# nse5310-module.net
KiCad netlist of a schematic drawn in Altium Designer
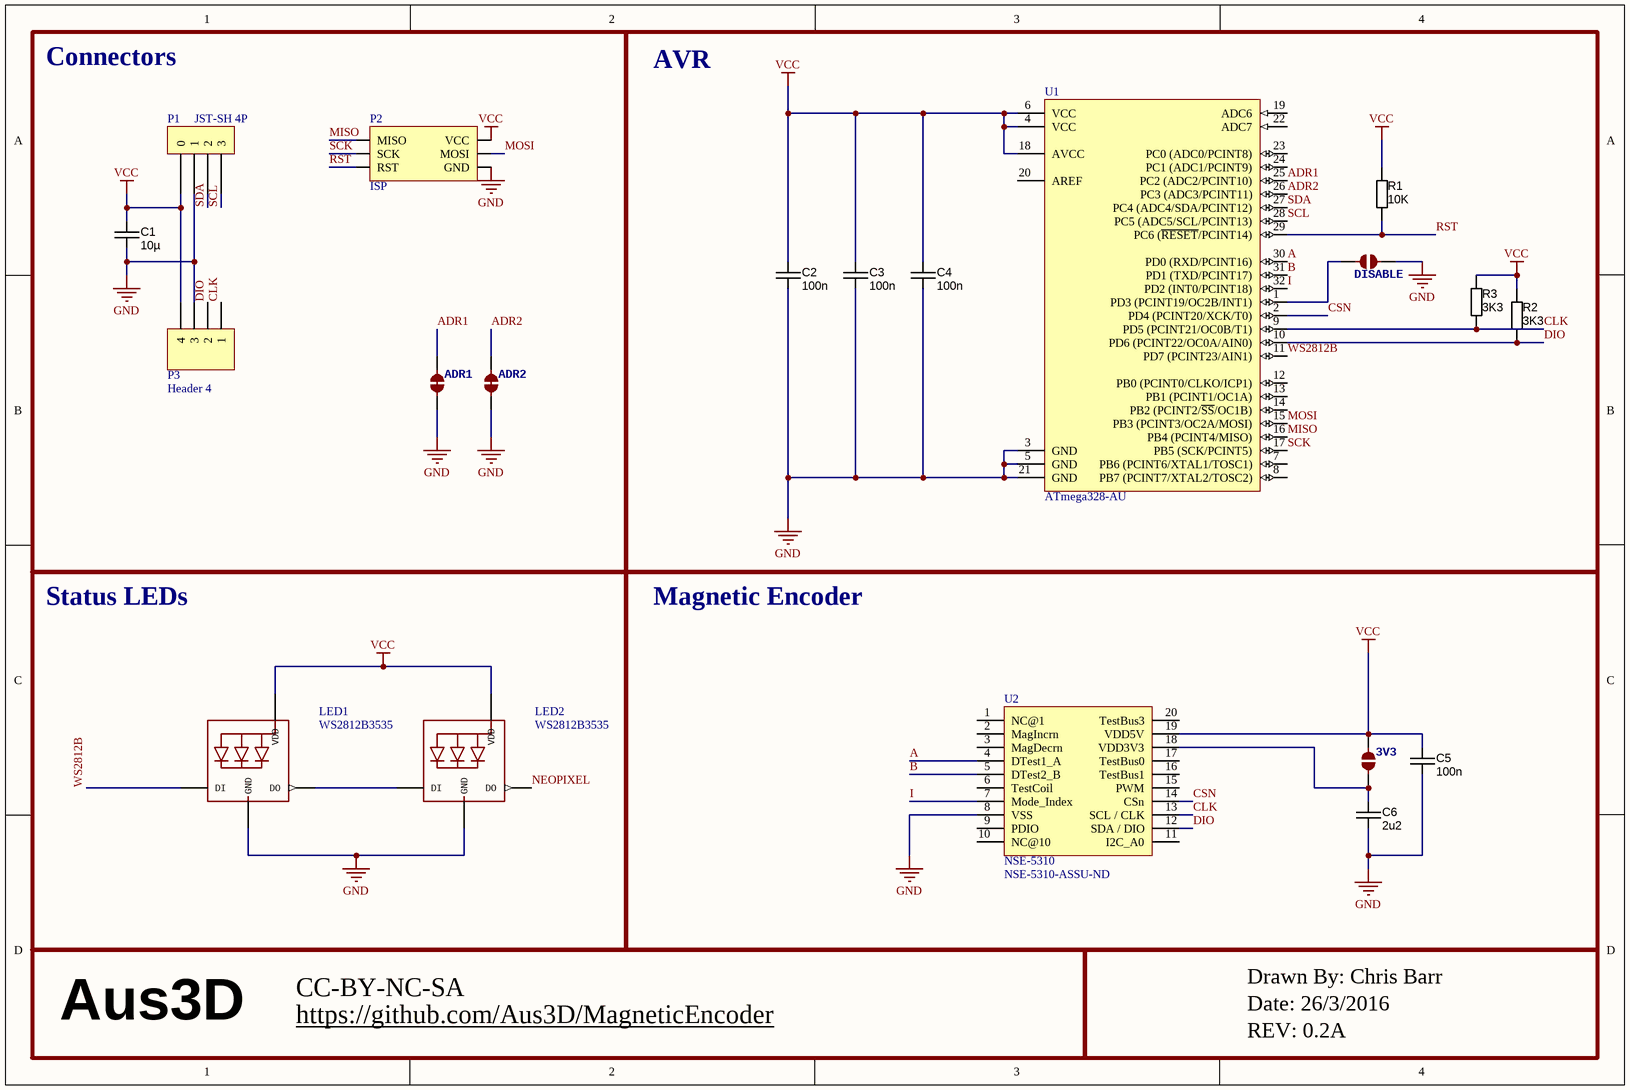
[diagram p0: nse5310-module.SchDoc]

(export (version "E")
  (design (tool "Eeschema 10.0.6"))
  (components
    (comp (ref "3V3")
      (value "JUMPER-PAD-2-NO")
      (footprint "PAD-JUMPER-2-NO_NO_SILK")
      (libsource (lib "SparkFun-Passives") (part "JUMPER-PAD-2-NO"))
    )
    (comp (ref "ADR1")
      (value "JUMPER-PAD-2-NC_BY_TRACE")
      (footprint "PAD-JUMPER-2-NC_BY_TRACE_YES_SILK")
      (libsource (lib "SparkFun-Passives") (part "JUMPER-PAD-2-NC_BY_TRACE"))
    )
    (comp (ref "ADR2")
      (value "JUMPER-PAD-2-NC_BY_TRACE")
      (footprint "PAD-JUMPER-2-NC_BY_TRACE_YES_SILK")
      (libsource (lib "SparkFun-Passives") (part "JUMPER-PAD-2-NC_BY_TRACE"))
    )
    (comp (ref "C1")
      (value "10µ")
      (footprint "CAPC2012X135N")
      (description "Capacitor SMD Cer 10uF 10% 10V X5R 0805")
      (fields (field (name "TOLERANCE") "±10%") (field (name "Comment") "approved sub OK"))
      (libsource (lib "PBL - Capacitors") (part "CAPC_10u_0805_10V"))
    )
    (comp (ref "C2")
      (value "100n")
      (footprint "CAPC1608X90N")
      (description "Capacitor SMD Cer 100nF 10% 50V X7R 0603")
      (fields (field (name "TOLERANCE") "±10%") (field (name "Comment") "approved sub OK"))
      (libsource (lib "PBL - Capacitors") (part "CAPC_100n_0603_X7R_50V_10%"))
    )
    (comp (ref "C3")
      (value "100n")
      (footprint "CAPC1608X90N")
      (description "Capacitor SMD Cer 100nF 10% 50V X7R 0603")
      (fields (field (name "TOLERANCE") "±10%") (field (name "Comment") "approved sub OK"))
      (libsource (lib "PBL - Capacitors") (part "CAPC_100n_0603_X7R_50V_10%"))
    )
    (comp (ref "C4")
      (value "100n")
      (footprint "CAPC1608X90N")
      (description "Capacitor SMD Cer 100nF 10% 50V X7R 0603")
      (fields (field (name "TOLERANCE") "±10%") (field (name "Comment") "approved sub OK"))
      (libsource (lib "PBL - Capacitors") (part "CAPC_100n_0603_X7R_50V_10%"))
    )
    (comp (ref "C5")
      (value "100n")
      (footprint "CAPC1608X90N")
      (description "Capacitor SMD Cer 100nF 10% 50V X7R 0603")
      (fields (field (name "TOLERANCE") "±10%") (field (name "Comment") "approved sub OK"))
      (libsource (lib "PBL - Capacitors") (part "CAPC_100n_0603_X7R_50V_10%"))
    )
    (comp (ref "C6")
      (value "2u2")
      (footprint "CAPC1608X90N")
      (description "Capacitor SMD Cer 2.2uF 10% 10V X5R 0603")
      (fields (field (name "TOLERANCE") "±10%") (field (name "Comment") "approved sub OK"))
      (libsource (lib "PBL - Capacitors") (part "CAPC_2u2_0603_10V_10%"))
    )
    (comp (ref "DISABLE")
      (value "JUMPER-PAD-2-NO")
      (footprint "PAD-JUMPER-2-NO_NO_SILK")
      (libsource (lib "SparkFun-Passives") (part "JUMPER-PAD-2-NO"))
    )
    (comp (ref "LED1")
      (value "WS2812B3535")
      (footprint "LED3535")
      (libsource (lib "adafruit") (part "WS2812B3535"))
    )
    (comp (ref "LED2")
      (value "WS2812B3535")
      (footprint "LED3535")
      (libsource (lib "adafruit") (part "WS2812B3535"))
    )
    (comp (ref "P1")
      (value "JST-SH 4P")
      (footprint "SM04B-SRSS-TB")
      (libsource (lib "Schlib1") (part "SM04B-SRSS-TB"))
    )
    (comp (ref "P2") (value "ISP") (footprint "ICSP Pads") (libsource (lib "Schlib1") (part "ISP Header")))
    (comp (ref "P3")
      (value "Header 4")
      (footprint "HDR1X4")
      (description "Header, 4-Pin")
      (fields (field (name "PUBLISHER") "Altium Limited"))
      (libsource (lib "Miscellaneous Connectors") (part "Header 4"))
    )
    (comp (ref "R1")
      (value "10K")
      (footprint "RESC1608X55N")
      (description "Resistor SMD chip 10k Ohm 0.1W 5% 0603")
      (fields (field (name "TOLERANCE") "±5%") (field (name "Comment") "Thick Film"))
      (libsource (lib "PBL - Resistors") (part "RES_10K_0603_5%"))
    )
    (comp (ref "R2")
      (value "3K3")
      (footprint "RESC1608X55N")
      (description "Resistor SMD chip 3.3k Ohm 0.1W 5% 0603")
      (fields (field (name "TOLERANCE") "±5%") (field (name "Comment") "Thick Film"))
      (libsource (lib "PBL - Resistors") (part "RES_3K3_0603_5%"))
    )
    (comp (ref "R3")
      (value "3K3")
      (footprint "RESC1608X55N")
      (description "Resistor SMD chip 3.3k Ohm 0.1W 5% 0603")
      (fields (field (name "TOLERANCE") "±5%") (field (name "Comment") "Thick Film"))
      (libsource (lib "PBL - Resistors") (part "RES_3K3_0603_5%"))
    )
    (comp (ref "U1")
      (value "ATmega328-AU")
      (footprint "32A_N")
      (libsource (lib "Atmel Microcontroller megaAVR") (part "ATmega328-AU"))
    )
    (comp (ref "U2")
      (value "NSE-5310")
      (footprint "NSE-5310")
      (fields (field (name "SUPPLIER PART NUMBER 1") "NSE-5310-ASSU-ND"))
      (libsource (lib "Schlib1") (part "NSE-5310"))
    )
  )
  (nets
    (net (code "1") (name "/A") (class "Default")
      (node (ref "U1") (pin "30") (pinfunction "PD0_(RXD/PCINT16)_30") (pintype "bidirectional"))
      (node (ref "U2") (pin "4") (pinfunction "DTest1_A_4") (pintype "passive"))
    )
    (net (code "2") (name "/ADR1") (class "Default")
      (node (ref "ADR1") (pin "2") (pinfunction "2_2") (pintype "passive"))
      (node (ref "U1") (pin "25") (pinfunction "PC2_(ADC2/PCINT10)_25") (pintype "bidirectional"))
    )
    (net (code "3") (name "/ADR2") (class "Default")
      (node (ref "ADR2") (pin "2") (pinfunction "2_2") (pintype "passive"))
      (node (ref "U1") (pin "26") (pinfunction "PC3_(ADC3/PCINT11)_26") (pintype "bidirectional"))
    )
    (net (code "4") (name "/B") (class "Default")
      (node (ref "U1") (pin "31") (pinfunction "PD1_(TXD/PCINT17)_31") (pintype "bidirectional"))
      (node (ref "U2") (pin "5") (pinfunction "DTest2_B_5") (pintype "passive"))
    )
    (net (code "5") (name "/CLK") (class "Default")
      (node (ref "P3") (pin "1") (pinfunction "1_1") (pintype "passive"))
      (node (ref "R3") (pin "2") (pinfunction "2_2") (pintype "passive"))
      (node (ref "U1") (pin "9") (pinfunction "PD5_(PCINT21/OC0B/T1)_9") (pintype "bidirectional"))
      (node (ref "U2") (pin "13") (pinfunction "SCL_/_CLK_13") (pintype "passive"))
    )
    (net (code "6") (name "/CSN") (class "Default")
      (node (ref "U1") (pin "2") (pinfunction "PD4_(PCINT20/XCK/T0)_2") (pintype "bidirectional"))
      (node (ref "U2") (pin "14") (pinfunction "CSn_14") (pintype "passive"))
    )
    (net (code "7") (name "/DIO") (class "Default")
      (node (ref "P3") (pin "2") (pinfunction "2_2") (pintype "passive"))
      (node (ref "R2") (pin "2") (pinfunction "2_2") (pintype "passive"))
      (node (ref "U1") (pin "10") (pinfunction "PD6_(PCINT22/OC0A/AIN0)_10") (pintype "bidirectional"))
      (node (ref "U2") (pin "12") (pinfunction "SDA_/_DIO_12") (pintype "passive"))
    )
    (net (code "8") (name "/I") (class "Default")
      (node (ref "U1") (pin "32") (pinfunction "PD2_(INT0/PCINT18)_32") (pintype "bidirectional"))
      (node (ref "U2") (pin "7") (pinfunction "Mode_Index_7") (pintype "passive"))
    )
    (net (code "9") (name "/MISO") (class "Default")
      (node (ref "P2") (pin "0") (pinfunction "MISO_0") (pintype "passive"))
      (node (ref "U1") (pin "16") (pinfunction "PB4_(PCINT4/MISO)_16") (pintype "bidirectional"))
    )
    (net (code "10") (name "/MOSI") (class "Default")
      (node (ref "P2") (pin "3") (pinfunction "MOSI_3") (pintype "passive"))
      (node (ref "U1") (pin "15") (pinfunction "PB3_(PCINT3/OC2A/MOSI)_15") (pintype "bidirectional"))
    )
    (net (code "11") (name "/NEOPIXEL") (class "Default")
      (node (ref "LED2") (pin "3") (pinfunction "DO_3") (pintype "output"))
    )
    (net (code "12") (name "/RST") (class "Default")
      (node (ref "P2") (pin "4") (pinfunction "RST_4") (pintype "passive"))
      (node (ref "R1") (pin "2") (pinfunction "2_2") (pintype "passive"))
      (node (ref "U1") (pin "29") (pinfunction "PC6_(~{RESET}/PCINT14)_29") (pintype "bidirectional"))
    )
    (net (code "13") (name "/SCK") (class "Default")
      (node (ref "P2") (pin "2") (pinfunction "SCK_2") (pintype "passive"))
      (node (ref "U1") (pin "17") (pinfunction "PB5_(SCK/PCINT5)_17") (pintype "bidirectional"))
    )
    (net (code "14") (name "/SCL") (class "Default")
      (node (ref "P1") (pin "3") (pinfunction "3_3") (pintype "passive"))
      (node (ref "U1") (pin "28") (pinfunction "PC5_(ADC5/SCL/PCINT13)_28") (pintype "bidirectional"))
    )
    (net (code "15") (name "/SDA") (class "Default")
      (node (ref "P1") (pin "2") (pinfunction "2_2") (pintype "passive"))
      (node (ref "U1") (pin "27") (pinfunction "PC4_(ADC4/SDA/PCINT12)_27") (pintype "bidirectional"))
    )
    (net (code "16") (name "/WS2812B") (class "Default")
      (node (ref "LED1") (pin "1") (pinfunction "DI_1") (pintype "passive"))
      (node (ref "U1") (pin "11") (pinfunction "PD7_(PCINT23/AIN1)_11") (pintype "bidirectional"))
    )
    (net (code "17") (name "GND") (class "Default")
      (node (ref "ADR1") (pin "1") (pinfunction "1_1") (pintype "passive"))
      (node (ref "ADR2") (pin "1") (pinfunction "1_1") (pintype "passive"))
      (node (ref "C1") (pin "2") (pintype "passive"))
      (node (ref "C2") (pin "2") (pintype "passive"))
      (node (ref "C3") (pin "2") (pintype "passive"))
      (node (ref "C4") (pin "2") (pintype "passive"))
      (node (ref "C5") (pin "2") (pintype "passive"))
      (node (ref "C6") (pin "2") (pintype "passive"))
      (node (ref "DISABLE") (pin "1") (pinfunction "1_1") (pintype "passive"))
      (node (ref "LED1") (pin "4") (pinfunction "GND_4") (pintype "power_in"))
      (node (ref "LED2") (pin "4") (pinfunction "GND_4") (pintype "power_in"))
      (node (ref "P1") (pin "1") (pinfunction "1_1") (pintype "passive"))
      (node (ref "P2") (pin "5") (pinfunction "GND_5") (pintype "passive"))
      (node (ref "P3") (pin "3") (pinfunction "3_3") (pintype "passive"))
      (node (ref "U1") (pin "21") (pinfunction "GND_21") (pintype "power_in"))
      (node (ref "U1") (pin "3") (pinfunction "GND_3") (pintype "power_in"))
      (node (ref "U1") (pin "5") (pinfunction "GND_5") (pintype "power_in"))
      (node (ref "U2") (pin "8") (pinfunction "VSS_8") (pintype "passive"))
    )
    (net (code "18") (name "Net-(LED1-DO)") (class "Default")
      (node (ref "LED1") (pin "3") (pinfunction "DO_3") (pintype "output"))
      (node (ref "LED2") (pin "1") (pinfunction "DI_1") (pintype "passive"))
    )
    (net (code "19") (name "Net-(U1-PD3_(PCINT19{slash}OC2B{slash}INT1))") (class "Default")
      (node (ref "DISABLE") (pin "2") (pinfunction "2_2") (pintype "passive"))
      (node (ref "U1") (pin "1") (pinfunction "PD3_(PCINT19/OC2B/INT1)_1") (pintype "bidirectional"))
    )
    (net (code "20") (name "Net-(U2-VDD3V3)") (class "Default")
      (node (ref "3V3") (pin "1") (pinfunction "1_1") (pintype "passive"))
      (node (ref "C6") (pin "1") (pintype "passive"))
      (node (ref "U2") (pin "18") (pinfunction "VDD3V3_18") (pintype "passive"))
    )
    (net (code "21") (name "VCC") (class "Default")
      (node (ref "3V3") (pin "2") (pinfunction "2_2") (pintype "passive"))
      (node (ref "C1") (pin "1") (pintype "passive"))
      (node (ref "C2") (pin "1") (pintype "passive"))
      (node (ref "C3") (pin "1") (pintype "passive"))
      (node (ref "C4") (pin "1") (pintype "passive"))
      (node (ref "C5") (pin "1") (pintype "passive"))
      (node (ref "LED1") (pin "2") (pinfunction "VDD_2") (pintype "power_in"))
      (node (ref "LED2") (pin "2") (pinfunction "VDD_2") (pintype "power_in"))
      (node (ref "P1") (pin "0") (pinfunction "0_0") (pintype "passive"))
      (node (ref "P2") (pin "1") (pinfunction "VCC_1") (pintype "passive"))
      (node (ref "P3") (pin "4") (pinfunction "4_4") (pintype "passive"))
      (node (ref "R1") (pin "1") (pinfunction "1_1") (pintype "passive"))
      (node (ref "R2") (pin "1") (pinfunction "1_1") (pintype "passive"))
      (node (ref "R3") (pin "1") (pinfunction "1_1") (pintype "passive"))
      (node (ref "U1") (pin "18") (pinfunction "AVCC_18") (pintype "power_in"))
      (node (ref "U1") (pin "4") (pinfunction "VCC_4") (pintype "power_in"))
      (node (ref "U1") (pin "6") (pinfunction "VCC_6") (pintype "power_in"))
      (node (ref "U2") (pin "19") (pinfunction "VDD5V_19") (pintype "passive"))
    )
    (net (code "22") (name "unconnected-(U1-ADC6-Pad19)") (class "Default")
      (node (ref "U1") (pin "19") (pinfunction "ADC6_19") (pintype "input"))
    )
    (net (code "23") (name "unconnected-(U1-ADC7-Pad22)") (class "Default")
      (node (ref "U1") (pin "22") (pinfunction "ADC7_22") (pintype "input"))
    )
    (net (code "24") (name "unconnected-(U1-AREF-Pad20)") (class "Default")
      (node (ref "U1") (pin "20") (pinfunction "AREF_20") (pintype "passive"))
    )
    (net (code "25") (name "unconnected-(U1-PB0_(PCINT0{slash}CLKO{slash}ICP1)-Pad12)") (class "Default")
      (node (ref "U1") (pin "12") (pinfunction "PB0_(PCINT0/CLKO/ICP1)_12") (pintype "bidirectional"))
    )
    (net (code "26") (name "unconnected-(U1-PB1_(PCINT1{slash}OC1A)-Pad13)") (class "Default")
      (node (ref "U1") (pin "13") (pinfunction "PB1_(PCINT1/OC1A)_13") (pintype "bidirectional"))
    )
    (net (code "27") (name "unconnected-(U1-PB2_(PCINT2{slash}~{SS}{slash}OC1B)-Pad14)") (class "Default")
      (node (ref "U1") (pin "14") (pinfunction "PB2_(PCINT2/~{SS}/OC1B)_14") (pintype "bidirectional"))
    )
    (net (code "28") (name "unconnected-(U1-PB6_(PCINT6{slash}XTAL1{slash}TOSC1)-Pad7)") (class "Default")
      (node (ref "U1") (pin "7") (pinfunction "PB6_(PCINT6/XTAL1/TOSC1)_7") (pintype "bidirectional"))
    )
    (net (code "29") (name "unconnected-(U1-PB7_(PCINT7{slash}XTAL2{slash}TOSC2)-Pad8)") (class "Default")
      (node (ref "U1") (pin "8") (pinfunction "PB7_(PCINT7/XTAL2/TOSC2)_8") (pintype "bidirectional"))
    )
    (net (code "30") (name "unconnected-(U1-PC0_(ADC0{slash}PCINT8)-Pad23)") (class "Default")
      (node (ref "U1") (pin "23") (pinfunction "PC0_(ADC0/PCINT8)_23") (pintype "bidirectional"))
    )
    (net (code "31") (name "unconnected-(U1-PC1_(ADC1{slash}PCINT9)-Pad24)") (class "Default")
      (node (ref "U1") (pin "24") (pinfunction "PC1_(ADC1/PCINT9)_24") (pintype "bidirectional"))
    )
    (net (code "32") (name "unconnected-(U2-I2C_A0-Pad11)") (class "Default")
      (node (ref "U2") (pin "11") (pinfunction "I2C_A0_11") (pintype "passive"))
    )
    (net (code "33") (name "unconnected-(U2-MagDecrn-Pad3)") (class "Default")
      (node (ref "U2") (pin "3") (pinfunction "MagDecrn_3") (pintype "passive"))
    )
    (net (code "34") (name "unconnected-(U2-MagIncrn-Pad2)") (class "Default")
      (node (ref "U2") (pin "2") (pinfunction "MagIncrn_2") (pintype "passive"))
    )
    (net (code "35") (name "unconnected-(U2-NC@1-Pad1)") (class "Default")
      (node (ref "U2") (pin "1") (pinfunction "NC@1_1") (pintype "passive"))
    )
    (net (code "36") (name "unconnected-(U2-NC@10-Pad10)") (class "Default")
      (node (ref "U2") (pin "10") (pinfunction "NC@10_10") (pintype "passive"))
    )
    (net (code "37") (name "unconnected-(U2-PDIO-Pad9)") (class "Default")
      (node (ref "U2") (pin "9") (pinfunction "PDIO_9") (pintype "passive"))
    )
    (net (code "38") (name "unconnected-(U2-PWM-Pad15)") (class "Default")
      (node (ref "U2") (pin "15") (pinfunction "PWM_15") (pintype "passive"))
    )
    (net (code "39") (name "unconnected-(U2-TestBus0-Pad17)") (class "Default")
      (node (ref "U2") (pin "17") (pinfunction "TestBus0_17") (pintype "passive"))
    )
    (net (code "40") (name "unconnected-(U2-TestBus1-Pad16)") (class "Default")
      (node (ref "U2") (pin "16") (pinfunction "TestBus1_16") (pintype "passive"))
    )
    (net (code "41") (name "unconnected-(U2-TestBus3-Pad20)") (class "Default")
      (node (ref "U2") (pin "20") (pinfunction "TestBus3_20") (pintype "passive"))
    )
    (net (code "42") (name "unconnected-(U2-TestCoil-Pad6)") (class "Default")
      (node (ref "U2") (pin "6") (pinfunction "TestCoil_6") (pintype "passive"))
    )
  )
)
